# Sensor_Board.net
KiCad netlist of a schematic drawn in Altium Designer
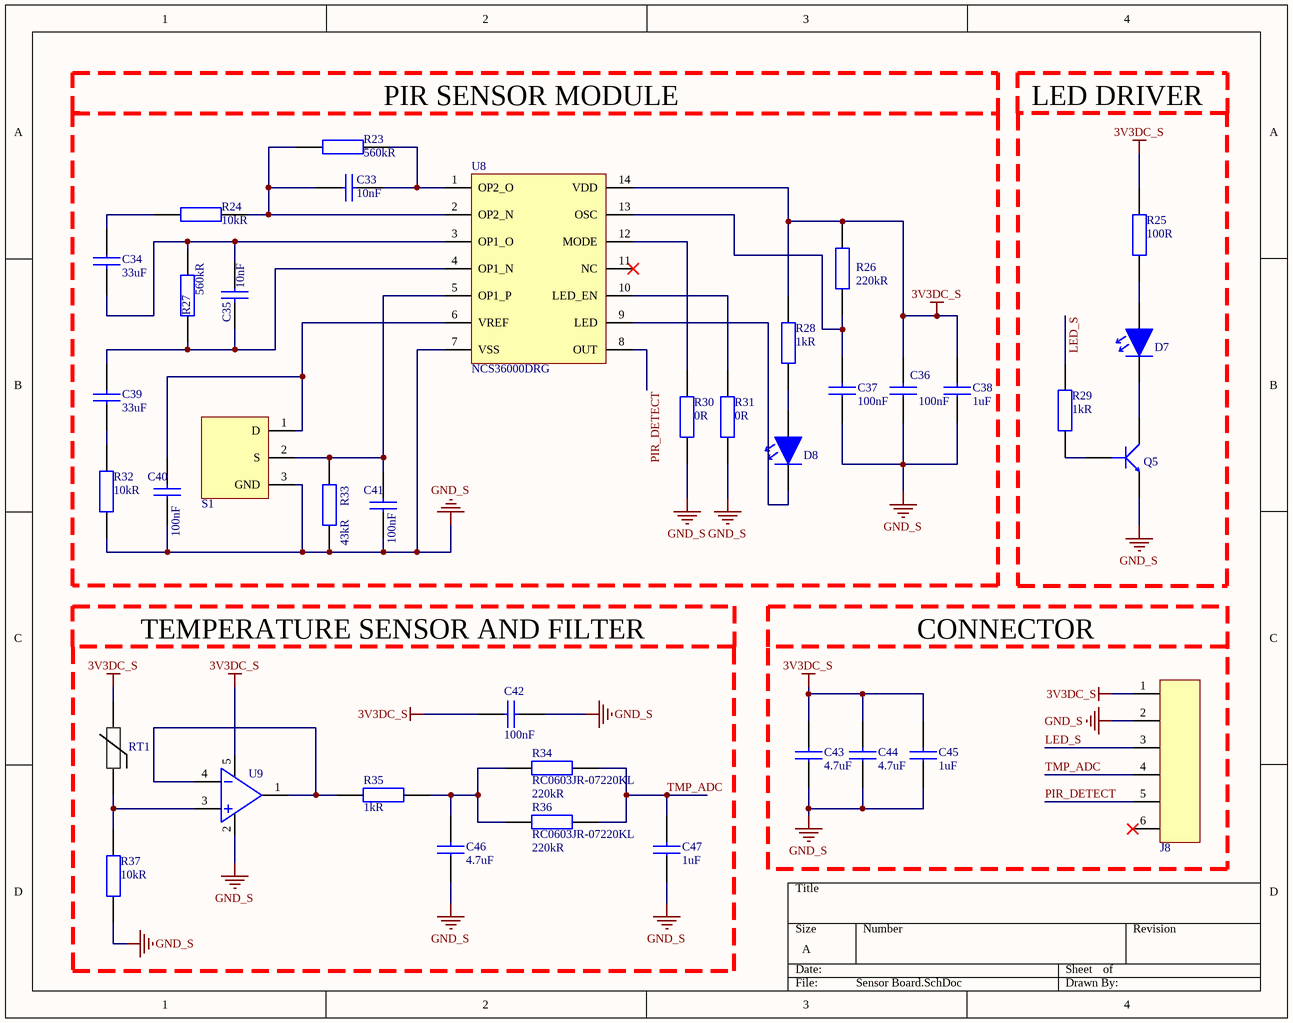
[diagram p0: Sensor Board.SchDoc]

(export (version "E")
  (design (tool "Eeschema 10.0.6"))
  (components
    (comp (ref "C33")
      (value "0603B103K160CT")
      (footprint "CAP_0603")
      (description "CAP CER 10nF %10 0603")
      (fields
        (field (name "MANUFACTURER") "Walsin Technologies")
        (field (name "TOLERANCE") "10%")
        (field (name "CAPACITANCE") "10nF")
        (field (name "DESIGNED BY") "BERK")
      )
      (libsource (lib "UDEMY_Library") (part "CAP CER 10nF 0603"))
    )
    (comp (ref "C34")
      (value "C3216X5R1E336M160AC")
      (footprint "CAP_1206")
      (description "CAP CER 33uF %20 1206 SMD")
      (fields
        (field (name "MANUFACTURER") "TDK")
        (field (name "TOLERANCE") "20%")
        (field (name "CAPACITANCE") "33uF")
        (field (name "DESIGNED BY") "BERK")
      )
      (libsource (lib "UDEMY_Library") (part "CAP CER 33uF 1206"))
    )
    (comp (ref "C35")
      (value "0603B103K160CT")
      (footprint "CAP_0603")
      (description "CAP CER 10nF %10 0603")
      (fields
        (field (name "MANUFACTURER") "Walsin Technologies")
        (field (name "TOLERANCE") "10%")
        (field (name "CAPACITANCE") "10nF")
        (field (name "DESIGNED BY") "BERK")
      )
      (libsource (lib "UDEMY_Library") (part "CAP CER 10nF 0603"))
    )
    (comp (ref "C36")
      (value "C0603C104K5RACTU")
      (footprint "CAP_0603")
      (description "CAP CER 100nF %10 0603 SMD")
      (fields
        (field (name "MANUFACTURER") "KEMET")
        (field (name "TOLERANCE") "10%")
        (field (name "CAPACITANCE") "100nF")
        (field (name "DESIGNED BY") "BERK")
      )
      (libsource (lib "UDEMY_Library") (part "CAP CER 100nF 0603"))
    )
    (comp (ref "C37")
      (value "C0603C104K5RACTU")
      (footprint "CAP_0603")
      (description "CAP CER 100nF %10 0603 SMD")
      (fields
        (field (name "MANUFACTURER") "KEMET")
        (field (name "TOLERANCE") "10%")
        (field (name "CAPACITANCE") "100nF")
        (field (name "DESIGNED BY") "BERK")
      )
      (libsource (lib "UDEMY_Library") (part "CAP CER 100nF 0603"))
    )
    (comp (ref "C38")
      (value "CL21B105KBFNNNE")
      (footprint "CAP_0805")
      (description "CAP CER 1uF %10 0805")
      (fields
        (field (name "MANUFACTURER") "Samsung")
        (field (name "TOLERANCE") "10%")
        (field (name "CAPACITANCE") "1uF")
        (field (name "DESIGNED BY") "BERK")
      )
      (libsource (lib "UDEMY_Library") (part "CAP CER 1uF 0805"))
    )
    (comp (ref "C39")
      (value "C3216X5R1E336M160AC")
      (footprint "CAP_1206")
      (description "CAP CER 33uF %20 1206 SMD")
      (fields
        (field (name "MANUFACTURER") "TDK")
        (field (name "TOLERANCE") "20%")
        (field (name "CAPACITANCE") "33uF")
        (field (name "DESIGNED BY") "BERK")
      )
      (libsource (lib "UDEMY_Library") (part "CAP CER 33uF 1206"))
    )
    (comp (ref "C40")
      (value "C0603C104K5RACTU")
      (footprint "CAP_0603")
      (description "CAP CER 100nF %10 0603 SMD")
      (fields
        (field (name "MANUFACTURER") "KEMET")
        (field (name "TOLERANCE") "10%")
        (field (name "CAPACITANCE") "100nF")
        (field (name "DESIGNED BY") "BERK")
      )
      (libsource (lib "UDEMY_Library") (part "CAP CER 100nF 0603"))
    )
    (comp (ref "C41")
      (value "C0603C104K5RACTU")
      (footprint "CAP_0603")
      (description "CAP CER 100nF %10 0603 SMD")
      (fields
        (field (name "MANUFACTURER") "KEMET")
        (field (name "TOLERANCE") "10%")
        (field (name "CAPACITANCE") "100nF")
        (field (name "DESIGNED BY") "BERK")
      )
      (libsource (lib "UDEMY_Library") (part "CAP CER 100nF 0603"))
    )
    (comp (ref "C42")
      (value "CL21B104KBCNNNC")
      (footprint "CAP_0805")
      (description "CAP CER 100nF %10 0805")
      (fields
        (field (name "MANUFACTURER") "Samsung")
        (field (name "TOLERANCE") "10%")
        (field (name "CAPACITANCE") "100nF")
        (field (name "DESIGNED BY") "BERK")
      )
      (libsource (lib "UDEMY_Library") (part "CAP CER 100nF 0805"))
    )
    (comp (ref "C43")
      (value "CL21A475KAQNNNE")
      (footprint "CAP_0805")
      (description "CAP CER 4.7uF %10 0805")
      (fields
        (field (name "MANUFACTURER") "Samsung")
        (field (name "TOLERANCE") "10%")
        (field (name "CAPACITANCE") "4.7uF")
        (field (name "DESIGNED BY") "BERK")
      )
      (libsource (lib "UDEMY_Library") (part "CAP CER 4.7uF 0805"))
    )
    (comp (ref "C44")
      (value "CL21A475KAQNNNE")
      (footprint "CAP_0805")
      (description "CAP CER 4.7uF %10 0805")
      (fields
        (field (name "MANUFACTURER") "Samsung")
        (field (name "TOLERANCE") "10%")
        (field (name "CAPACITANCE") "4.7uF")
        (field (name "DESIGNED BY") "BERK")
      )
      (libsource (lib "UDEMY_Library") (part "CAP CER 4.7uF 0805"))
    )
    (comp (ref "C45")
      (value "CL21B105KBFNNNE")
      (footprint "CAP_0805")
      (description "CAP CER 1uF %10 0805")
      (fields
        (field (name "MANUFACTURER") "Samsung")
        (field (name "TOLERANCE") "10%")
        (field (name "CAPACITANCE") "1uF")
        (field (name "DESIGNED BY") "BERK")
      )
      (libsource (lib "UDEMY_Library") (part "CAP CER 1uF 0805"))
    )
    (comp (ref "C46")
      (value "CL21A475KAQNNNE")
      (footprint "CAP_0805")
      (description "CAP CER 4.7uF %10 0805")
      (fields
        (field (name "MANUFACTURER") "Samsung")
        (field (name "TOLERANCE") "10%")
        (field (name "CAPACITANCE") "4.7uF")
        (field (name "DESIGNED BY") "BERK")
      )
      (libsource (lib "UDEMY_Library") (part "CAP CER 4.7uF 0805"))
    )
    (comp (ref "C47")
      (value "CL21B105KBFNNNE")
      (footprint "CAP_0805")
      (description "CAP CER 1uF %10 0805")
      (fields
        (field (name "MANUFACTURER") "Samsung")
        (field (name "TOLERANCE") "10%")
        (field (name "CAPACITANCE") "1uF")
        (field (name "DESIGNED BY") "BERK")
      )
      (libsource (lib "UDEMY_Library") (part "CAP CER 1uF 0805"))
    )
    (comp (ref "D7")
      (value "LH R974-LP-1")
      (footprint "LED_RED_0805")
      (description "LED Uni-Color Hyper Red 660nm 2-Pin Chip 0805(2012Metric) T/R")
      (fields (field (name "MANUFACTURER") "Osram Opto") (field (name "DESIGNED BY") "BERK"))
      (libsource (lib "UDEMY_Library") (part "LED RED 0805"))
    )
    (comp (ref "D8")
      (value "LTST-C171GKT")
      (footprint "LED_GREEN_0805")
      (description "Green 0805 130 º Min 5 mcd Typical 12 mcd Water Clear Lens SMT LED")
      (fields (field (name "MANUFACTURER") "Vishay Lite-On") (field (name "DESIGNED BY") "BERK"))
      (libsource (lib "UDEMY_Library") (part "LED GREEN 0805"))
    )
    (comp (ref "J8")
      (value "64800611622")
      (footprint "64800611622")
      (description "1.50mm 6PIN Connector")
      (fields (field (name "MANUFACTURER") "Wurth Electronics"))
      (libsource (lib "UDEMY_Library") (part "64800611622_conn_6pin"))
    )
    (comp (ref "Q5")
      (value "MMBT3904-7-F")
      (footprint "SOT-23F")
      (description "Transistor General Purpose BJT NPN 40 Volt 0.2A Automotive 3-Pin SOT-23")
      (fields (field (name "MANUFACTURER") "Diodes Zetex") (field (name "DESIGNED BY") "BERK"))
      (libsource (lib "UDEMY_Library") (part "MMBT3904-7-F"))
    )
    (comp (ref "R23")
      (value "RC0603JR-07560KL")
      (footprint "RES_0603")
      (description "RES SMD 560K OHM 5% 1/10W 0603")
      (fields
        (field (name "MANUFACTURER") "Yageo")
        (field (name "TOLERANCE") "5%")
        (field (name "RESISTANCE") "560kR")
        (field (name "DESIGNED BY") "BERK")
      )
      (libsource (lib "UDEMY_Library") (part "RES 560K OHM 0603"))
    )
    (comp (ref "R24")
      (value "RC0603FR-0710KL")
      (footprint "RES_0603")
      (description "RES 10K %1 OHM 0603 SMD")
      (fields
        (field (name "MANUFACTURER") "Yageo")
        (field (name "TOLERANCE") "1%")
        (field (name "RESISTANCE") "10kR")
        (field (name "DESIGNED BY") "BERK")
      )
      (libsource (lib "") (part "RES 10K OHM 0603_1"))
    )
    (comp (ref "R25")
      (value "RC0603JR-07100RL")
      (footprint "RES_0603")
      (description "RES 100 %5 OHM 0603 SMD")
      (fields
        (field (name "MANUFACTURER") "Yageo")
        (field (name "TOLERANCE") "5%")
        (field (name "RESISTANCE") "100R")
        (field (name "DESIGNED BY") "BERK")
      )
      (libsource (lib "UDEMY_Library") (part "RES 100 OHM 0603"))
    )
    (comp (ref "R26")
      (value "RC0603JR-07220KL")
      (footprint "RES_0603")
      (description "RES 220K %5 OHM 0603 SMD")
      (fields
        (field (name "MANUFACTURER") "Yageo")
        (field (name "TOLERANCE") "5%")
        (field (name "RESISTANCE") "220kR")
      )
      (libsource (lib "") (part "RES 220K OHM 0603_1"))
    )
    (comp (ref "R27")
      (value "RC0603JR-07560KL")
      (footprint "RES_0603")
      (description "RES SMD 560K OHM 5% 1/10W 0603")
      (fields
        (field (name "MANUFACTURER") "Yageo")
        (field (name "TOLERANCE") "5%")
        (field (name "RESISTANCE") "560kR")
        (field (name "DESIGNED BY") "BERK")
      )
      (libsource (lib "") (part "RES 560K OHM 0603_1"))
    )
    (comp (ref "R28")
      (value "RC0603FR-0710KL")
      (footprint "RES_0603")
      (description "RES 1K %1 OHM 0603 SMD")
      (fields
        (field (name "MANUFACTURER") "Yageo")
        (field (name "MANUFACTURER PART NUMBER") "RC0603JR-071KL")
        (field (name "RESISTANCE") "1kR")
        (field (name "DESIGNED BY") "BERK")
      )
      (libsource (lib "UDEMY_Library") (part "RES 1K OHM 0603"))
    )
    (comp (ref "R29")
      (value "RC0603FR-0710KL")
      (footprint "RES_0603")
      (description "RES 1K %1 OHM 0603 SMD")
      (fields
        (field (name "MANUFACTURER") "Yageo")
        (field (name "MANUFACTURER PART NUMBER") "RC0603JR-071KL")
        (field (name "RESISTANCE") "1kR")
        (field (name "DESIGNED BY") "BERK")
      )
      (libsource (lib "") (part "RES 1K OHM 0603_2"))
    )
    (comp (ref "R30")
      (value "RC0603JR-070RL")
      (footprint "RES_0603")
      (description "RES 0 %1 OHM 0603 SMD")
      (fields
        (field (name "MANUFACTURER") "Yageo")
        (field (name "TOLERANCE") "1%")
        (field (name "RESISTANCE") "0R")
        (field (name "DESIGNED BY") "BERK")
      )
      (libsource (lib "UDEMY_Library") (part "RES 0 OHM 0603"))
    )
    (comp (ref "R31")
      (value "RC0603JR-070RL")
      (footprint "RES_0603")
      (description "RES 0 %1 OHM 0603 SMD")
      (fields
        (field (name "MANUFACTURER") "Yageo")
        (field (name "TOLERANCE") "1%")
        (field (name "RESISTANCE") "0R")
        (field (name "DESIGNED BY") "BERK")
      )
      (libsource (lib "UDEMY_Library") (part "RES 0 OHM 0603"))
    )
    (comp (ref "R32")
      (value "RC0603FR-0710KL")
      (footprint "RES_0603")
      (description "RES 10K %1 OHM 0603 SMD")
      (fields
        (field (name "MANUFACTURER") "Yageo")
        (field (name "TOLERANCE") "1%")
        (field (name "RESISTANCE") "10kR")
        (field (name "DESIGNED BY") "BERK")
      )
      (libsource (lib "UDEMY_Library") (part "RES 10K OHM 0603"))
    )
    (comp (ref "R33")
      (value "RC0603JR-0743KL")
      (footprint "RES_0603")
      (description "RES 43K %5 OHM 0603 SMD")
      (fields
        (field (name "MANUFACTURER") "Yageo")
        (field (name "TOLERANCE") "5%")
        (field (name "RESISTANCE") "43kR")
        (field (name "DESIGNED BY") "BERK")
      )
      (libsource (lib "UDEMY_Library") (part "RES 43K OHM 0603"))
    )
    (comp (ref "R34")
      (value "RC0603JR-07220KL")
      (footprint "RES_0603")
      (description "RES 220K %5 OHM 0603 SMD")
      (fields
        (field (name "MANUFACTURER") "Yageo")
        (field (name "TOLERANCE") "5%")
        (field (name "RESISTANCE") "220kR")
      )
      (libsource (lib "UDEMY_Library") (part "RES 220K OHM 0603"))
    )
    (comp (ref "R35")
      (value "RC0603FR-0710KL")
      (footprint "RES_0603")
      (description "RES 1K %1 OHM 0603 SMD")
      (fields
        (field (name "MANUFACTURER") "Yageo")
        (field (name "MANUFACTURER PART NUMBER") "RC0603JR-071KL")
        (field (name "RESISTANCE") "1kR")
        (field (name "DESIGNED BY") "BERK")
      )
      (libsource (lib "") (part "RES 1K OHM 0603_1"))
    )
    (comp (ref "R36")
      (value "RC0603JR-07220KL")
      (footprint "RES_0603")
      (description "RES 220K %5 OHM 0603 SMD")
      (fields
        (field (name "MANUFACTURER") "Yageo")
        (field (name "TOLERANCE") "5%")
        (field (name "RESISTANCE") "220kR")
      )
      (libsource (lib "UDEMY_Library") (part "RES 220K OHM 0603"))
    )
    (comp (ref "R37")
      (value "RC0603FR-0710KL")
      (footprint "RES_0603")
      (description "RES 10K %1 OHM 0603 SMD")
      (fields
        (field (name "MANUFACTURER") "Yageo")
        (field (name "TOLERANCE") "1%")
        (field (name "RESISTANCE") "10kR")
        (field (name "DESIGNED BY") "BERK")
      )
      (libsource (lib "UDEMY_Library") (part "RES 10K OHM 0603"))
    )
    (comp (ref "RT1")
      (value "TFPT1206L1002FM")
      (footprint "RES_1206")
      (description "Thermistor PTC 10K Ohm 1% 1206")
      (fields
        (field (name "MANUFACTURER") "Vishay Dale")
        (field (name "TOLERANCE") "1%")
        (field (name "DESIGNED BY") "BERK")
      )
      (libsource (lib "UDEMY_Library") (part "TFPT1206L1002FM"))
    )
    (comp (ref "S1")
      (value "LHI 878/3902")
      (footprint "LHI 878")
      (description "SENSOR PYRO DETECTOR DUAL MOTION")
      (fields (field (name "DESIGNED BY") "BERK"))
      (libsource (lib "UDEMY_Library") (part "LHI 878/3902"))
    )
    (comp (ref "U8")
      (value "NCS36000DRG")
      (footprint "SOIC14")
      (description "PIR Controller Low Noise Amplifiers and LDO Regulator 14-Pin SOIC N T/R")
      (fields (field (name "MANUFACTURER") "ON Semiconductor") (field (name "DESIGNED BY") "BERK"))
      (libsource (lib "UDEMY_Library") (part "NCS36000"))
    )
    (comp (ref "U9")
      (value "OPA314AIDBVR")
      (footprint "SOT23-5")
      (description "Op Amp OPA314")
      (fields (field (name "MANUFACTURER") "Texas Instruments") (field (name "DESIGNED BY") "BERK"))
      (libsource (lib "UDEMY_Library") (part "OPA314"))
    )
  )
  (nets
    (net (code "1") (name "/LED_S") (class "Default")
      (node (ref "J8") (pin "3") (pintype "power_in"))
      (node (ref "R29") (pin "1") (pinfunction "1_1") (pintype "passive"))
    )
    (net (code "2") (name "/PIR_DETECT") (class "Default")
      (node (ref "J8") (pin "5") (pintype "power_in"))
      (node (ref "U8") (pin "8") (pinfunction "OUT_8") (pintype "passive"))
    )
    (net (code "3") (name "/TMP_ADC") (class "Default")
      (node (ref "C47") (pin "2") (pinfunction "2_2") (pintype "passive"))
      (node (ref "J8") (pin "4") (pintype "power_in"))
      (node (ref "R34") (pin "2") (pinfunction "2_2") (pintype "passive"))
      (node (ref "R36") (pin "2") (pinfunction "2_2") (pintype "passive"))
    )
    (net (code "4") (name "3V3DC_S") (class "Default")
      (node (ref "C36") (pin "2") (pinfunction "2_2") (pintype "passive"))
      (node (ref "C38") (pin "2") (pinfunction "2_2") (pintype "passive"))
      (node (ref "C42") (pin "1") (pinfunction "1_1") (pintype "passive"))
      (node (ref "C43") (pin "2") (pinfunction "2_2") (pintype "passive"))
      (node (ref "C44") (pin "2") (pinfunction "2_2") (pintype "passive"))
      (node (ref "C45") (pin "2") (pinfunction "2_2") (pintype "passive"))
      (node (ref "J8") (pin "1") (pintype "power_in"))
      (node (ref "R25") (pin "2") (pinfunction "2_2") (pintype "passive"))
      (node (ref "R26") (pin "2") (pinfunction "2_2") (pintype "passive"))
      (node (ref "R28") (pin "2") (pinfunction "2_2") (pintype "passive"))
      (node (ref "RT1") (pin "2") (pinfunction "2_2") (pintype "passive"))
      (node (ref "U8") (pin "14") (pinfunction "VDD_14") (pintype "passive"))
      (node (ref "U9") (pin "5") (pinfunction "5_5") (pintype "passive"))
    )
    (net (code "5") (name "GND_S") (class "Default")
      (node (ref "C36") (pin "1") (pinfunction "1_1") (pintype "passive"))
      (node (ref "C37") (pin "1") (pinfunction "1_1") (pintype "passive"))
      (node (ref "C38") (pin "1") (pinfunction "1_1") (pintype "passive"))
      (node (ref "C40") (pin "1") (pinfunction "1_1") (pintype "passive"))
      (node (ref "C41") (pin "1") (pinfunction "1_1") (pintype "passive"))
      (node (ref "C42") (pin "2") (pinfunction "2_2") (pintype "passive"))
      (node (ref "C43") (pin "1") (pinfunction "1_1") (pintype "passive"))
      (node (ref "C44") (pin "1") (pinfunction "1_1") (pintype "passive"))
      (node (ref "C45") (pin "1") (pinfunction "1_1") (pintype "passive"))
      (node (ref "C46") (pin "1") (pinfunction "1_1") (pintype "passive"))
      (node (ref "C47") (pin "1") (pinfunction "1_1") (pintype "passive"))
      (node (ref "J8") (pin "2") (pintype "power_in"))
      (node (ref "Q5") (pin "2") (pinfunction "E_2") (pintype "power_in"))
      (node (ref "R30") (pin "1") (pinfunction "1_1") (pintype "passive"))
      (node (ref "R31") (pin "1") (pinfunction "1_1") (pintype "passive"))
      (node (ref "R32") (pin "1") (pinfunction "1_1") (pintype "passive"))
      (node (ref "R33") (pin "1") (pinfunction "1_1") (pintype "passive"))
      (node (ref "R37") (pin "1") (pinfunction "1_1") (pintype "passive"))
      (node (ref "S1") (pin "3") (pinfunction "GND_3") (pintype "passive"))
      (node (ref "U8") (pin "7") (pinfunction "VSS_7") (pintype "passive"))
      (node (ref "U9") (pin "2") (pinfunction "2_2") (pintype "passive"))
    )
    (net (code "6") (name "Net-(C34-Pad1)") (class "Default")
      (node (ref "C34") (pin "1") (pinfunction "1_1") (pintype "passive"))
      (node (ref "R24") (pin "1") (pinfunction "1_1") (pintype "passive"))
    )
    (net (code "7") (name "Net-(C39-Pad1)") (class "Default")
      (node (ref "C39") (pin "1") (pinfunction "1_1") (pintype "passive"))
      (node (ref "R32") (pin "2") (pinfunction "2_2") (pintype "passive"))
    )
    (net (code "8") (name "Net-(C46-Pad2)") (class "Default")
      (node (ref "C46") (pin "2") (pinfunction "2_2") (pintype "passive"))
      (node (ref "R34") (pin "1") (pinfunction "1_1") (pintype "passive"))
      (node (ref "R35") (pin "2") (pinfunction "2_2") (pintype "passive"))
      (node (ref "R36") (pin "1") (pinfunction "1_1") (pintype "passive"))
    )
    (net (code "9") (name "Net-(D7-Pad2)") (class "Default")
      (node (ref "D7") (pin "2") (pinfunction "2_2") (pintype "power_in"))
      (node (ref "R25") (pin "1") (pinfunction "1_1") (pintype "passive"))
    )
    (net (code "10") (name "Net-(D8-Pad2)") (class "Default")
      (node (ref "D8") (pin "2") (pinfunction "2_2") (pintype "power_in"))
      (node (ref "R28") (pin "1") (pinfunction "1_1") (pintype "passive"))
    )
    (net (code "11") (name "Net-(Q5-B)") (class "Default")
      (node (ref "Q5") (pin "1") (pinfunction "B_1") (pintype "power_in"))
      (node (ref "R29") (pin "2") (pinfunction "2_2") (pintype "passive"))
    )
    (net (code "12") (name "Net-(Q5-C)") (class "Default")
      (node (ref "D7") (pin "1") (pinfunction "1_1") (pintype "power_in"))
      (node (ref "Q5") (pin "3") (pinfunction "C_3") (pintype "power_in"))
    )
    (net (code "13") (name "Net-(R35-Pad1)") (class "Default")
      (node (ref "R35") (pin "1") (pinfunction "1_1") (pintype "passive"))
      (node (ref "U9") (pin "1") (pinfunction "1_1") (pintype "passive"))
      (node (ref "U9") (pin "4") (pinfunction "4_4") (pintype "passive"))
    )
    (net (code "14") (name "Net-(R37-Pad2)") (class "Default")
      (node (ref "R37") (pin "2") (pinfunction "2_2") (pintype "passive"))
      (node (ref "RT1") (pin "1") (pinfunction "1_1") (pintype "passive"))
      (node (ref "U9") (pin "3") (pinfunction "3_3") (pintype "passive"))
    )
    (net (code "15") (name "Net-(S1-D)") (class "Default")
      (node (ref "C40") (pin "2") (pinfunction "2_2") (pintype "passive"))
      (node (ref "S1") (pin "1") (pinfunction "D_1") (pintype "passive"))
      (node (ref "U8") (pin "6") (pinfunction "VREF_6") (pintype "passive"))
    )
    (net (code "16") (name "Net-(S1-S)") (class "Default")
      (node (ref "C41") (pin "2") (pinfunction "2_2") (pintype "passive"))
      (node (ref "R33") (pin "2") (pinfunction "2_2") (pintype "passive"))
      (node (ref "S1") (pin "2") (pinfunction "S_2") (pintype "passive"))
      (node (ref "U8") (pin "5") (pinfunction "OP1_P_5") (pintype "passive"))
    )
    (net (code "17") (name "Net-(U8-LED)") (class "Default")
      (node (ref "D8") (pin "1") (pinfunction "1_1") (pintype "power_in"))
      (node (ref "U8") (pin "9") (pinfunction "LED_9") (pintype "passive"))
    )
    (net (code "18") (name "Net-(U8-LED_EN)") (class "Default")
      (node (ref "R31") (pin "2") (pinfunction "2_2") (pintype "passive"))
      (node (ref "U8") (pin "10") (pinfunction "LED_EN_10") (pintype "passive"))
    )
    (net (code "19") (name "Net-(U8-MODE)") (class "Default")
      (node (ref "R30") (pin "2") (pinfunction "2_2") (pintype "passive"))
      (node (ref "U8") (pin "12") (pinfunction "MODE_12") (pintype "passive"))
    )
    (net (code "20") (name "Net-(U8-OP1_N)") (class "Default")
      (node (ref "C35") (pin "2") (pinfunction "2_2") (pintype "passive"))
      (node (ref "C39") (pin "2") (pinfunction "2_2") (pintype "passive"))
      (node (ref "R27") (pin "1") (pinfunction "1_1") (pintype "passive"))
      (node (ref "U8") (pin "4") (pinfunction "OP1_N_4") (pintype "passive"))
    )
    (net (code "21") (name "Net-(U8-OP1_O)") (class "Default")
      (node (ref "C34") (pin "2") (pinfunction "2_2") (pintype "passive"))
      (node (ref "C35") (pin "1") (pinfunction "1_1") (pintype "passive"))
      (node (ref "R27") (pin "2") (pinfunction "2_2") (pintype "passive"))
      (node (ref "U8") (pin "3") (pinfunction "OP1_O_3") (pintype "passive"))
    )
    (net (code "22") (name "Net-(U8-OP2_N)") (class "Default")
      (node (ref "C33") (pin "1") (pinfunction "1_1") (pintype "passive"))
      (node (ref "R23") (pin "1") (pinfunction "1_1") (pintype "passive"))
      (node (ref "R24") (pin "2") (pinfunction "2_2") (pintype "passive"))
      (node (ref "U8") (pin "2") (pinfunction "OP2_N_2") (pintype "passive"))
    )
    (net (code "23") (name "Net-(U8-OP2_O)") (class "Default")
      (node (ref "C33") (pin "2") (pinfunction "2_2") (pintype "passive"))
      (node (ref "R23") (pin "2") (pinfunction "2_2") (pintype "passive"))
      (node (ref "U8") (pin "1") (pinfunction "OP2_O_1") (pintype "passive"))
    )
    (net (code "24") (name "Net-(U8-OSC)") (class "Default")
      (node (ref "C37") (pin "2") (pinfunction "2_2") (pintype "passive"))
      (node (ref "R26") (pin "1") (pinfunction "1_1") (pintype "passive"))
      (node (ref "U8") (pin "13") (pinfunction "OSC_13") (pintype "passive"))
    )
    (net (code "25") (name "unconnected-(J8-Pad6)") (class "Default")
      (node (ref "J8") (pin "6") (pintype "power_in+no_connect"))
    )
    (net (code "26") (name "unconnected-(U8-NC-Pad11)") (class "Default")
      (node (ref "U8") (pin "11") (pinfunction "NC_11") (pintype "passive+no_connect"))
    )
  )
)
